# 6-Power.net
KiCad netlist of a schematic drawn in Altium Designer
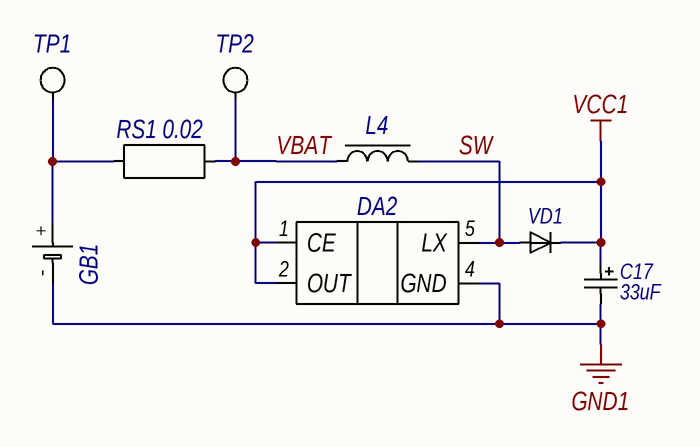
[diagram p0: 6-Power.SchDoc]

(export (version "E")
  (design (tool "Eeschema 10.0.6"))
  (components
    (comp (ref "C17")
      (value "33uF")
      (footprint "CAP_TYPE_A")
      (description "Конденсатор полярный")
      (fields (field (name "PARTNUMBER") "T491A336K006AT"))
      (libsource (lib "passive") (part "C_POL"))
    )
    (comp (ref "DA2")
      (value "NCP1400A")
      (footprint "SOT23-5")
      (description "PSIC, Low-Power Step-Up Converter")
      (fields (field (name "MFG") "ONS"))
      (libsource (lib "ic") (part "NCP1400A"))
    )
    (comp (ref "GB1")
      (value "Battery")
      (footprint "AAA Holder_1")
      (fields (field (name "PARTNUMBER") "Custom"))
      (libsource (lib "el_mech") (part "Battery"))
    )
    (comp (ref "L4")
      (value "~")
      (footprint "SRN5040")
      (description "Дроссель с сердечником")
      (fields (field (name "PARTNUMBER") "VLCF4028T-220MR72-2") (field (name "MFG") "TDK"))
      (libsource (lib "el_mag") (part "Ind_core"))
    )
    (comp (ref "RS1")
      (value "0.02")
      (footprint "CHIP_0805_R")
      (description "Резистор")
      (fields (field (name "PARTNUMBER") "0R02 0.5%"))
      (libsource (lib "RCL") (part "Резистор"))
    )
    (comp (ref "TP1") (value "TEST_POINT") (footprint "Pad_1") (libsource (lib "conn") (part "TEST_POINT")))
    (comp (ref "TP2") (value "TEST_POINT") (footprint "Pad_1") (libsource (lib "conn") (part "TEST_POINT")))
    (comp (ref "VD1")
      (value "STPS0520Z")
      (footprint "SOD123")
      (description "Диод")
      (fields (field (name "MFG") "ST"))
      (libsource (lib "semi") (part "Diode"))
    )
  )
  (nets
    (net (code "1") (name "/SW") (class "Default")
      (node (ref "DA2") (pin "5") (pinfunction "LX_5") (pintype "passive"))
      (node (ref "L4") (pin "2") (pinfunction "2_2") (pintype "passive"))
      (node (ref "VD1") (pin "A") (pinfunction "A_A") (pintype "passive"))
    )
    (net (code "2") (name "/VBAT") (class "Default")
      (node (ref "L4") (pin "1") (pinfunction "1_1") (pintype "passive"))
      (node (ref "RS1") (pin "2") (pinfunction "2_2") (pintype "passive"))
      (node (ref "TP2") (pin "1") (pintype "passive"))
    )
    (net (code "3") (name "GND1") (class "Default")
      (node (ref "C17") (pin "2") (pinfunction "2_2") (pintype "passive"))
      (node (ref "DA2") (pin "4") (pinfunction "GND_4") (pintype "passive"))
      (node (ref "GB1") (pin "-") (pintype "passive"))
    )
    (net (code "4") (name "Net-(GB1-Pad+)") (class "Default")
      (node (ref "GB1") (pin "+") (pintype "passive"))
      (node (ref "RS1") (pin "1") (pinfunction "1_1") (pintype "passive"))
      (node (ref "TP1") (pin "1") (pintype "passive"))
    )
    (net (code "5") (name "VCC1") (class "Default")
      (node (ref "C17") (pin "1") (pinfunction "1_1") (pintype "passive"))
      (node (ref "DA2") (pin "1") (pinfunction "CE_1") (pintype "passive"))
      (node (ref "DA2") (pin "2") (pinfunction "OUT_2") (pintype "passive"))
      (node (ref "VD1") (pin "K") (pinfunction "K_K") (pintype "passive"))
    )
  )
)
